# SCH_Card_Capacitive_without_capacitor_20.net
KiCad netlist of a schematic drawn in EasyEDA
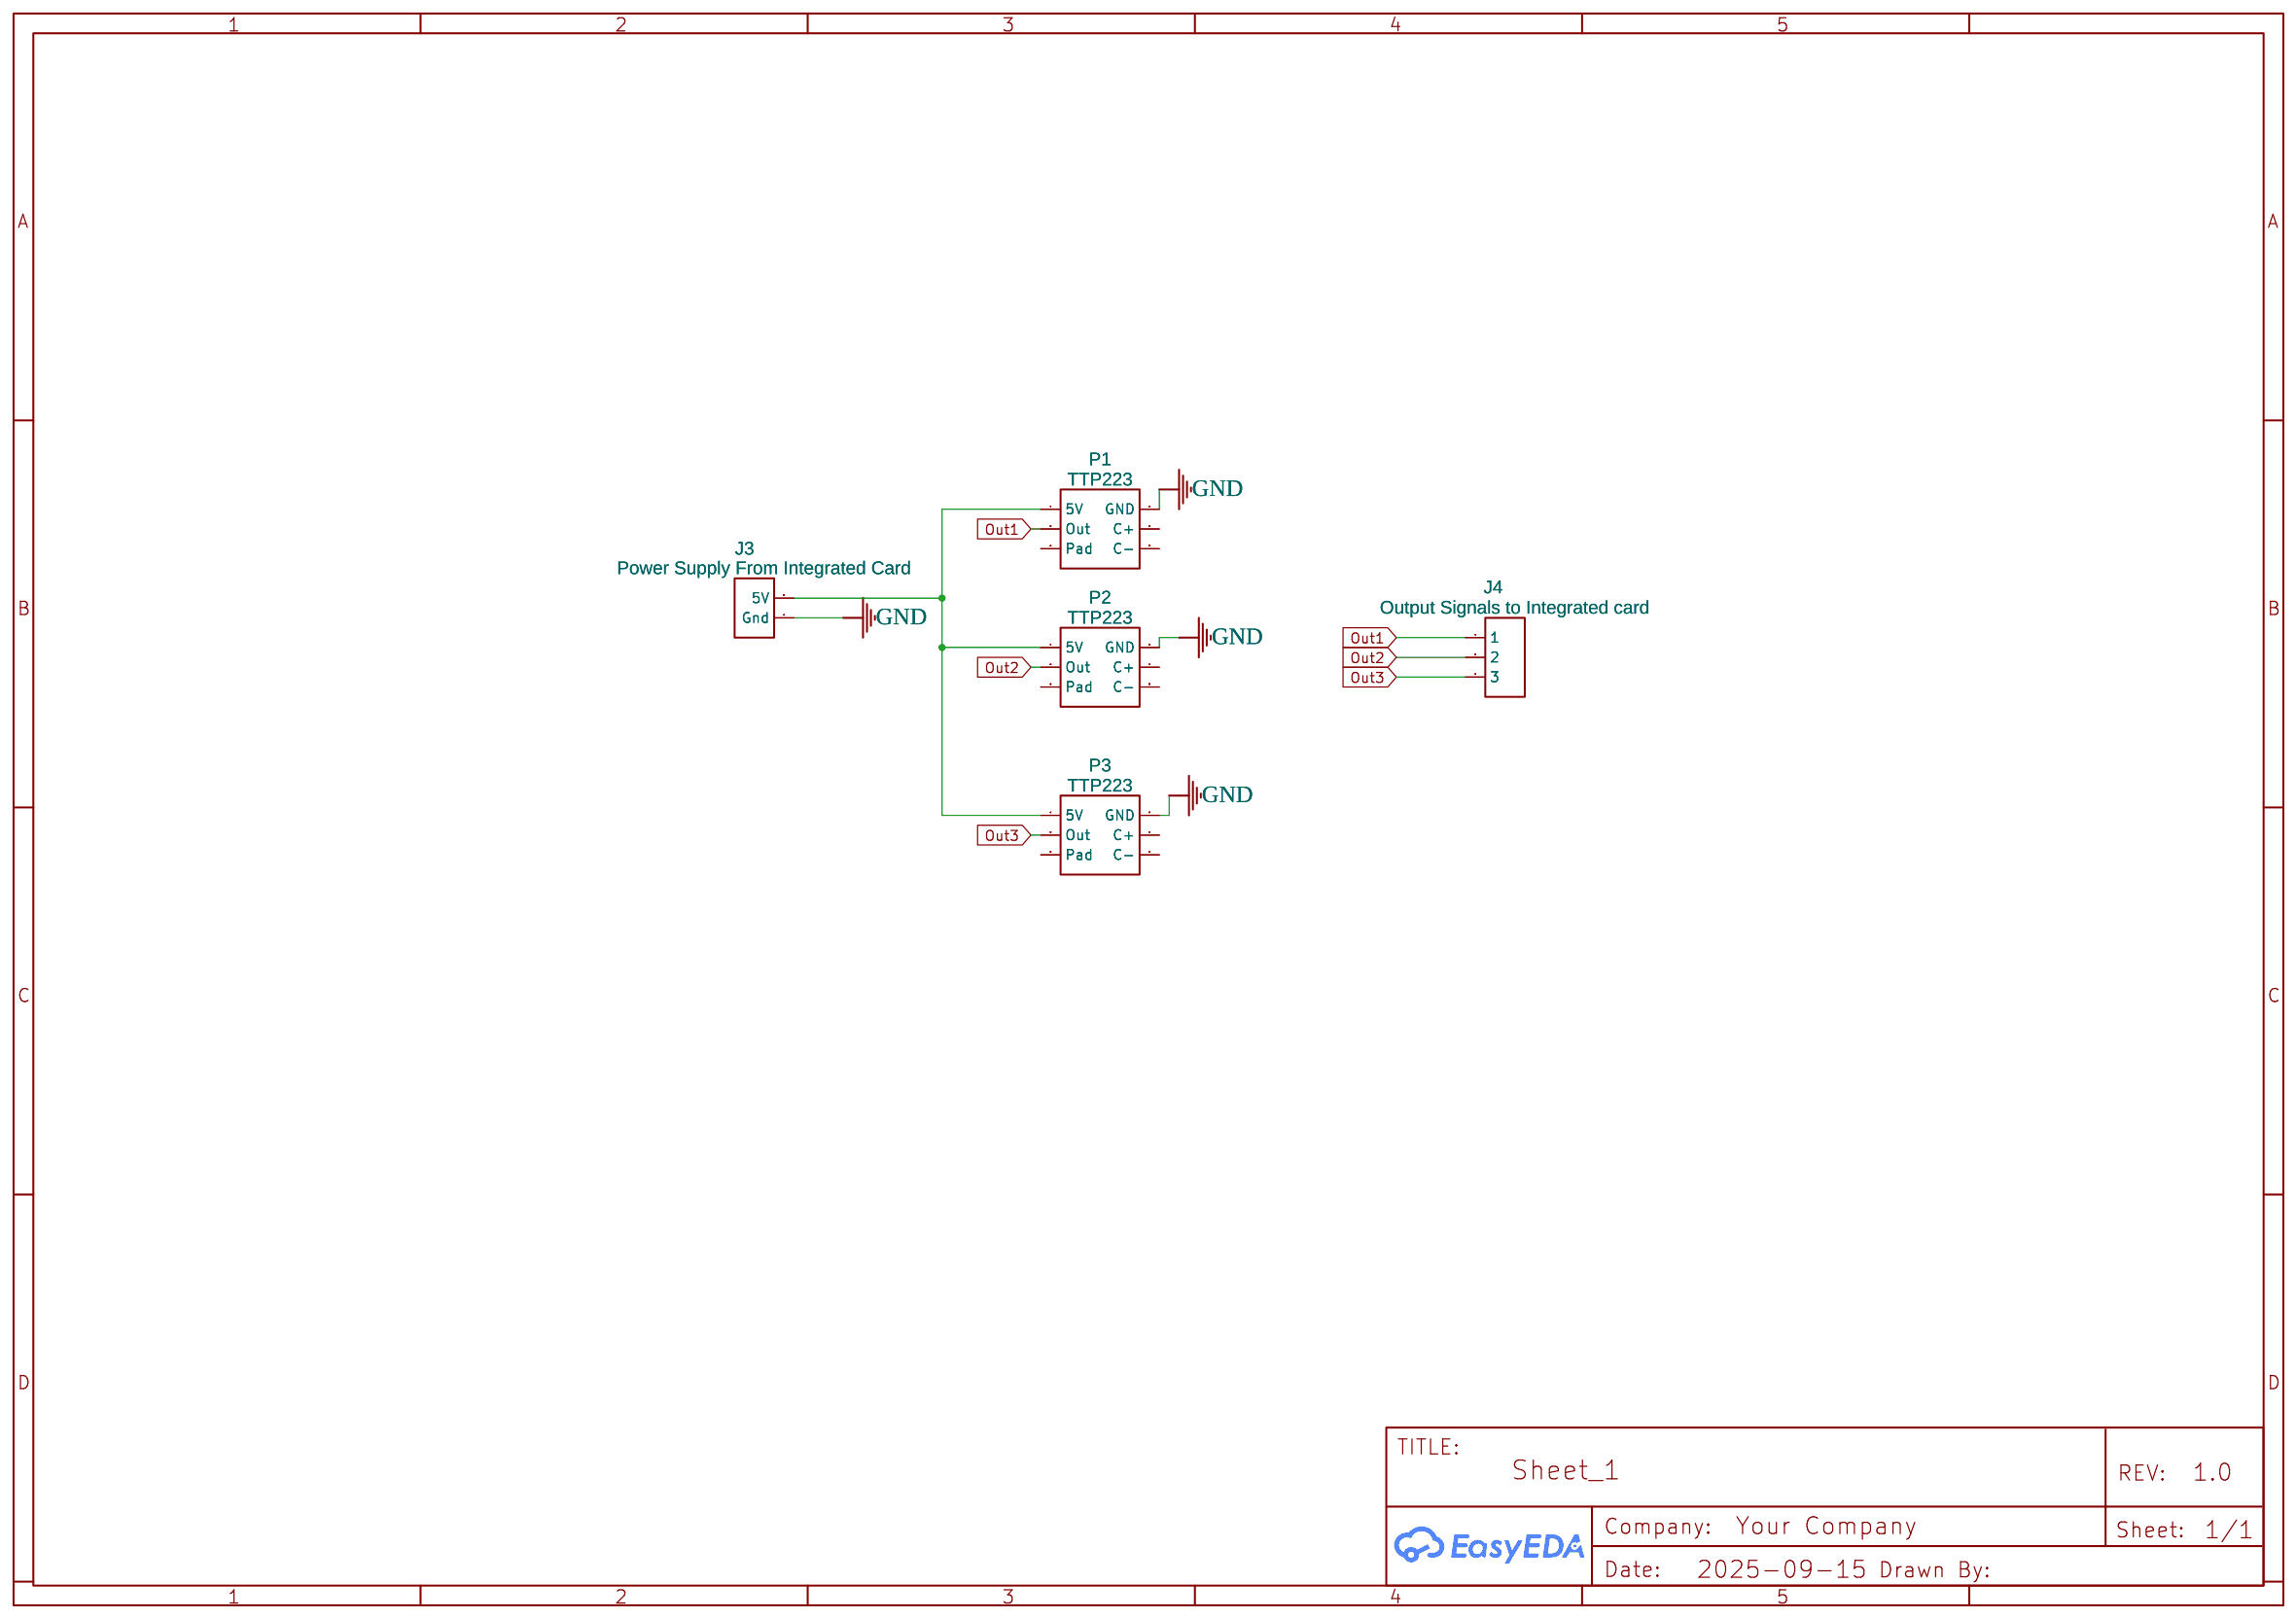
[diagram p0: schematic sheet]

(export (version "E")
  (design (tool "Eeschema 10.0.6"))
  (components
    (comp (ref "J3") (value "Power Supply From Integrated Card") (libsource (lib "") (part "HDR-M-2.54_1x2")))
    (comp (ref "J4") (value "Output Signals to Integrated card") (libsource (lib "") (part "HDR-M-2.54_1x3")))
    (comp (ref "P1")
      (value "TTP223")
      (fields (field (name "Manufacturer Part") "2X3 2.54mm IDC Box") (field (name "Manufacturer") "BOOMELE"))
      (libsource (lib "") (part "HDR-IDC-2.54-2X3P"))
    )
    (comp (ref "P2")
      (value "TTP223")
      (fields (field (name "Manufacturer Part") "2X3 2.54mm IDC Box") (field (name "Manufacturer") "BOOMELE"))
      (libsource (lib "") (part "HDR-IDC-2.54-2X3P"))
    )
    (comp (ref "P3")
      (value "TTP223")
      (fields (field (name "Manufacturer Part") "2X3 2.54mm IDC Box") (field (name "Manufacturer") "BOOMELE"))
      (libsource (lib "") (part "HDR-IDC-2.54-2X3P"))
    )
  )
  (nets
    (net (code "1") (name "GND") (class "Default")
      (node (ref "J3") (pin "1") (pinfunction "Gnd_1") (pintype "unspecified"))
      (node (ref "P1") (pin "2") (pinfunction "GND_2") (pintype "unspecified"))
      (node (ref "P2") (pin "2") (pinfunction "GND_2") (pintype "unspecified"))
      (node (ref "P3") (pin "2") (pinfunction "GND_2") (pintype "unspecified"))
    )
    (net (code "2") (name "Net-(J3-5V)") (class "Default")
      (node (ref "J3") (pin "2") (pinfunction "5V_2") (pintype "unspecified"))
      (node (ref "P1") (pin "1") (pinfunction "5V_1") (pintype "unspecified"))
      (node (ref "P2") (pin "1") (pinfunction "5V_1") (pintype "unspecified"))
      (node (ref "P3") (pin "1") (pinfunction "5V_1") (pintype "unspecified"))
    )
    (net (code "3") (name "Out1") (class "Default")
      (node (ref "J4") (pin "1") (pinfunction "1_1") (pintype "input"))
      (node (ref "P1") (pin "3") (pinfunction "Out_3") (pintype "unspecified"))
    )
    (net (code "4") (name "Out2") (class "Default")
      (node (ref "J4") (pin "2") (pinfunction "2_2") (pintype "input"))
      (node (ref "P2") (pin "3") (pinfunction "Out_3") (pintype "unspecified"))
    )
    (net (code "5") (name "Out3") (class "Default")
      (node (ref "J4") (pin "3") (pinfunction "3_3") (pintype "input"))
      (node (ref "P3") (pin "3") (pinfunction "Out_3") (pintype "unspecified"))
    )
    (net (code "6") (name "unconnected-(P1-C+-Pad4)") (class "Default")
      (node (ref "P1") (pin "4") (pinfunction "C+_4") (pintype "unspecified"))
    )
    (net (code "7") (name "unconnected-(P1-C--Pad6)") (class "Default")
      (node (ref "P1") (pin "6") (pinfunction "C-_6") (pintype "unspecified"))
    )
    (net (code "8") (name "unconnected-(P1-Pad-Pad5)") (class "Default")
      (node (ref "P1") (pin "5") (pinfunction "Pad_5") (pintype "unspecified"))
    )
    (net (code "9") (name "unconnected-(P2-C+-Pad4)") (class "Default")
      (node (ref "P2") (pin "4") (pinfunction "C+_4") (pintype "unspecified"))
    )
    (net (code "10") (name "unconnected-(P2-C--Pad6)") (class "Default")
      (node (ref "P2") (pin "6") (pinfunction "C-_6") (pintype "unspecified"))
    )
    (net (code "11") (name "unconnected-(P2-Pad-Pad5)") (class "Default")
      (node (ref "P2") (pin "5") (pinfunction "Pad_5") (pintype "unspecified"))
    )
    (net (code "12") (name "unconnected-(P3-C+-Pad4)") (class "Default")
      (node (ref "P3") (pin "4") (pinfunction "C+_4") (pintype "unspecified"))
    )
    (net (code "13") (name "unconnected-(P3-C--Pad6)") (class "Default")
      (node (ref "P3") (pin "6") (pinfunction "C-_6") (pintype "unspecified"))
    )
    (net (code "14") (name "unconnected-(P3-Pad-Pad5)") (class "Default")
      (node (ref "P3") (pin "5") (pinfunction "Pad_5") (pintype "unspecified"))
    )
  )
)
